# RF19_Sensor_CAN_Module_Power.net
KiCad netlist of a schematic drawn in Altium Designer
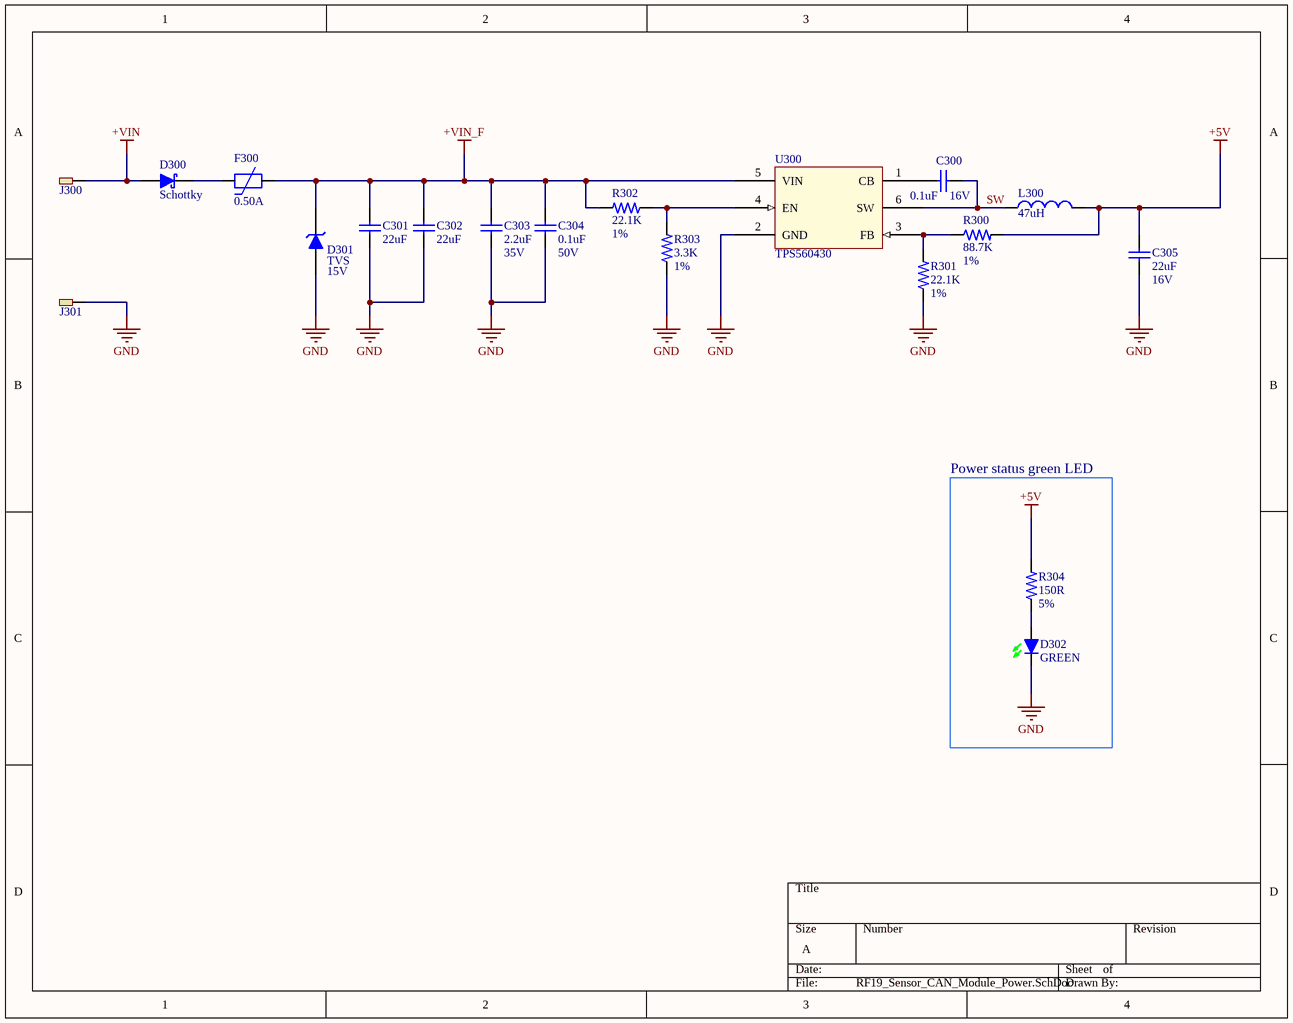
[diagram p0: RF19_Sensor_CAN_Module_Power.SchDoc]

(export (version "E")
  (design (tool "Eeschema 10.0.6"))
  (components
    (comp (ref "C300")
      (value "0.1uF")
      (footprint "C0402")
      (description "Ceramic cap, 0.1uF +/-10% 16V X5R 0402")
      (fields (field (name "VOLTAGE") "16V") (field (name "Comment") "C00U110P16VX5R0402"))
      (libsource (lib "Custom") (part "C00U110P16VX5R0402"))
    )
    (comp (ref "C301")
      (value "22uF")
      (footprint "C1206")
      (description "Ceramic capacitor")
      (fields (field (name "Comment") "CERAMIC CAP"))
      (libsource (lib "Custom") (part "CAP CERAMIC"))
    )
    (comp (ref "C302")
      (value "22uF")
      (footprint "C1206")
      (description "Ceramic capacitor")
      (fields (field (name "Comment") "CERAMIC CAP"))
      (libsource (lib "Custom") (part "CAP CERAMIC"))
    )
    (comp (ref "C303")
      (value "2.2uF")
      (footprint "C0603")
      (description "Ceramic cap, 2.2uF +/-10% 35V X5R 0603")
      (fields (field (name "VOLTAGE") "35V") (field (name "Comment") "C02U210P35VX5R0603"))
      (libsource (lib "Custom") (part "C02U210P35VX5R0603"))
    )
    (comp (ref "C304")
      (value "0.1uF")
      (footprint "C0603")
      (description "Ceramic cap, 0.1uF +/-10% 50V X7R 0603")
      (fields (field (name "VOLTAGE") "50V") (field (name "Comment") "CERAMIC CAP"))
      (libsource (lib "Custom") (part "C00U110P50VX7R0603"))
    )
    (comp (ref "C305")
      (value "22uF")
      (footprint "C0805")
      (description "Ceramic cap, 22uF +/-20% 16V X5R 0805")
      (fields (field (name "VOLTAGE") "16V") (field (name "Comment") "CERAMIC CAP"))
      (libsource (lib "Custom") (part "C022U20P16VX5R0805"))
    )
    (comp (ref "D300")
      (value "Schottky")
      (footprint "SOD-123W")
      (description "High speed Schottky Diode")
      (libsource (lib "Custom") (part "DIODE SCHOTTKY"))
    )
    (comp (ref "D301")
      (value "TVS")
      (footprint "DO-214AC")
      (description "TVS protection diode")
      (fields (field (name "ALTIUM_VALUE") "15V") (field (name "POWER") "1W"))
      (libsource (lib "Custom") (part "DIODE TVS"))
    )
    (comp (ref "D302")
      (value "GREEN")
      (footprint "0603 LED")
      (description "LED Green, 0603 2.0V 20mA")
      (libsource (lib "Custom") (part "D0603GREEN"))
    )
    (comp (ref "F300")
      (value "0.50A")
      (footprint "PTC 1206")
      (description "PTC RESETTBLE 0.50A 9V 0805")
      (libsource (lib "Custom") (part "PTC"))
    )
    (comp (ref "J300")
      (value "BREAKOUT")
      (footprint "BREAKOOUT PAD")
      (description "Breakout pad for later extension")
      (libsource (lib "Custom") (part "BREAKOUT"))
    )
    (comp (ref "J301")
      (value "BREAKOUT")
      (footprint "BREAKOOUT PAD")
      (description "Breakout pad for later extension")
      (libsource (lib "Custom") (part "BREAKOUT"))
    )
    (comp (ref "L300")
      (value "47uH")
      (footprint "SRN4018TA")
      (description "Inductor")
      (fields (field (name "PUBLISHER") "Altium Limited"))
      (libsource (lib "Miscellaneous Devices") (part "Inductor"))
    )
    (comp (ref "R300")
      (value "88.7K")
      (footprint "R0402")
      (description "Resistor 88.7K 1% 0402 1/16W")
      (fields (field (name "TOLERANCE") "1%") (field (name "Comment") "R88K710P0402063"))
      (libsource (lib "Custom") (part "R88K710P0402063"))
    )
    (comp (ref "R301")
      (value "22.1K")
      (footprint "R0402")
      (description "Resistor 22.1K 1% 0402 1/16W")
      (fields (field (name "TOLERANCE") "1%") (field (name "Comment") "R22K110P0402063"))
      (libsource (lib "Custom") (part "R22K110P0402063"))
    )
    (comp (ref "R302")
      (value "22.1K")
      (footprint "R0402")
      (description "Resistor 22.1K 1% 0402 1/16W")
      (fields (field (name "TOLERANCE") "1%") (field (name "Comment") "R22K110P0402063"))
      (libsource (lib "Custom") (part "R22K110P0402063"))
    )
    (comp (ref "R303")
      (value "3.3K")
      (footprint "R0402")
      (description "Resistor 3.3K 1% 0402 1/16W")
      (fields (field (name "TOLERANCE") "1%") (field (name "Comment") "R03K310P0402063"))
      (libsource (lib "Custom") (part "R03K310P0402063"))
    )
    (comp (ref "R304")
      (value "150R")
      (footprint "R0402")
      (description "Resistor 150R 5% 0402 1/16W")
      (fields (field (name "TOLERANCE") "5%") (field (name "Comment") "R150R50P0402063"))
      (libsource (lib "Custom") (part "R150R50P0402063"))
    )
    (comp (ref "U300")
      (value "TPS560430")
      (footprint "TI_SOP8_R-PDSO-G6")
      (libsource (lib "Custom") (part "TPS560430"))
    )
  )
  (nets
    (net (code "1") (name "+5V") (class "Default")
      (node (ref "C305") (pin "1") (pinfunction "1_1") (pintype "passive"))
      (node (ref "L300") (pin "2") (pinfunction "2_2") (pintype "passive"))
      (node (ref "R300") (pin "2") (pinfunction "2_2") (pintype "passive"))
      (node (ref "R304") (pin "2") (pinfunction "2_2") (pintype "passive"))
    )
    (net (code "2") (name "+VIN") (class "Default")
      (node (ref "D300") (pin "A") (pinfunction "A_A") (pintype "passive"))
      (node (ref "J300") (pin "1") (pinfunction "1_1") (pintype "passive"))
    )
    (net (code "3") (name "+VIN_F") (class "Default")
      (node (ref "C301") (pin "1") (pinfunction "1_1") (pintype "passive"))
      (node (ref "C302") (pin "1") (pinfunction "1_1") (pintype "passive"))
      (node (ref "C303") (pin "1") (pinfunction "1_1") (pintype "passive"))
      (node (ref "C304") (pin "1") (pinfunction "1_1") (pintype "passive"))
      (node (ref "D301") (pin "C") (pinfunction "C_C") (pintype "passive"))
      (node (ref "F300") (pin "2") (pinfunction "2_2") (pintype "passive"))
      (node (ref "R302") (pin "2") (pinfunction "2_2") (pintype "passive"))
      (node (ref "U300") (pin "5") (pinfunction "VIN_5") (pintype "power_in"))
    )
    (net (code "4") (name "/SW") (class "Default")
      (node (ref "C300") (pin "1") (pinfunction "1_1") (pintype "passive"))
      (node (ref "L300") (pin "1") (pinfunction "1_1") (pintype "passive"))
      (node (ref "U300") (pin "6") (pinfunction "SW_6") (pintype "power_in"))
    )
    (net (code "5") (name "GND") (class "Default")
      (node (ref "C301") (pin "2") (pinfunction "2_2") (pintype "passive"))
      (node (ref "C302") (pin "2") (pinfunction "2_2") (pintype "passive"))
      (node (ref "C303") (pin "2") (pinfunction "2_2") (pintype "passive"))
      (node (ref "C304") (pin "2") (pinfunction "2_2") (pintype "passive"))
      (node (ref "C305") (pin "2") (pinfunction "2_2") (pintype "passive"))
      (node (ref "D301") (pin "A") (pinfunction "A_A") (pintype "passive"))
      (node (ref "D302") (pin "C") (pinfunction "C_C") (pintype "passive"))
      (node (ref "J301") (pin "1") (pinfunction "1_1") (pintype "passive"))
      (node (ref "R301") (pin "1") (pinfunction "1_1") (pintype "passive"))
      (node (ref "R303") (pin "1") (pinfunction "1_1") (pintype "passive"))
      (node (ref "U300") (pin "2") (pinfunction "GND_2") (pintype "power_in"))
    )
    (net (code "6") (name "Net-(D300-PadC)") (class "Default")
      (node (ref "D300") (pin "C") (pinfunction "C_C") (pintype "passive"))
      (node (ref "F300") (pin "1") (pinfunction "1_1") (pintype "passive"))
    )
    (net (code "7") (name "Net-(D302-PadA)") (class "Default")
      (node (ref "D302") (pin "A") (pinfunction "A_A") (pintype "passive"))
      (node (ref "R304") (pin "1") (pinfunction "1_1") (pintype "passive"))
    )
    (net (code "8") (name "Net-(U300-CB)") (class "Default")
      (node (ref "C300") (pin "2") (pinfunction "2_2") (pintype "passive"))
      (node (ref "U300") (pin "1") (pinfunction "CB_1") (pintype "power_in"))
    )
    (net (code "9") (name "Net-(U300-EN)") (class "Default")
      (node (ref "R302") (pin "1") (pinfunction "1_1") (pintype "passive"))
      (node (ref "R303") (pin "2") (pinfunction "2_2") (pintype "passive"))
      (node (ref "U300") (pin "4") (pinfunction "EN_4") (pintype "input"))
    )
    (net (code "10") (name "Net-(U300-FB)") (class "Default")
      (node (ref "R300") (pin "1") (pinfunction "1_1") (pintype "passive"))
      (node (ref "R301") (pin "2") (pinfunction "2_2") (pintype "passive"))
      (node (ref "U300") (pin "3") (pinfunction "FB_3") (pintype "input"))
    )
  )
)
